# lfovca-rev2.net
KiCad netlist of a schematic drawn in EAGLE
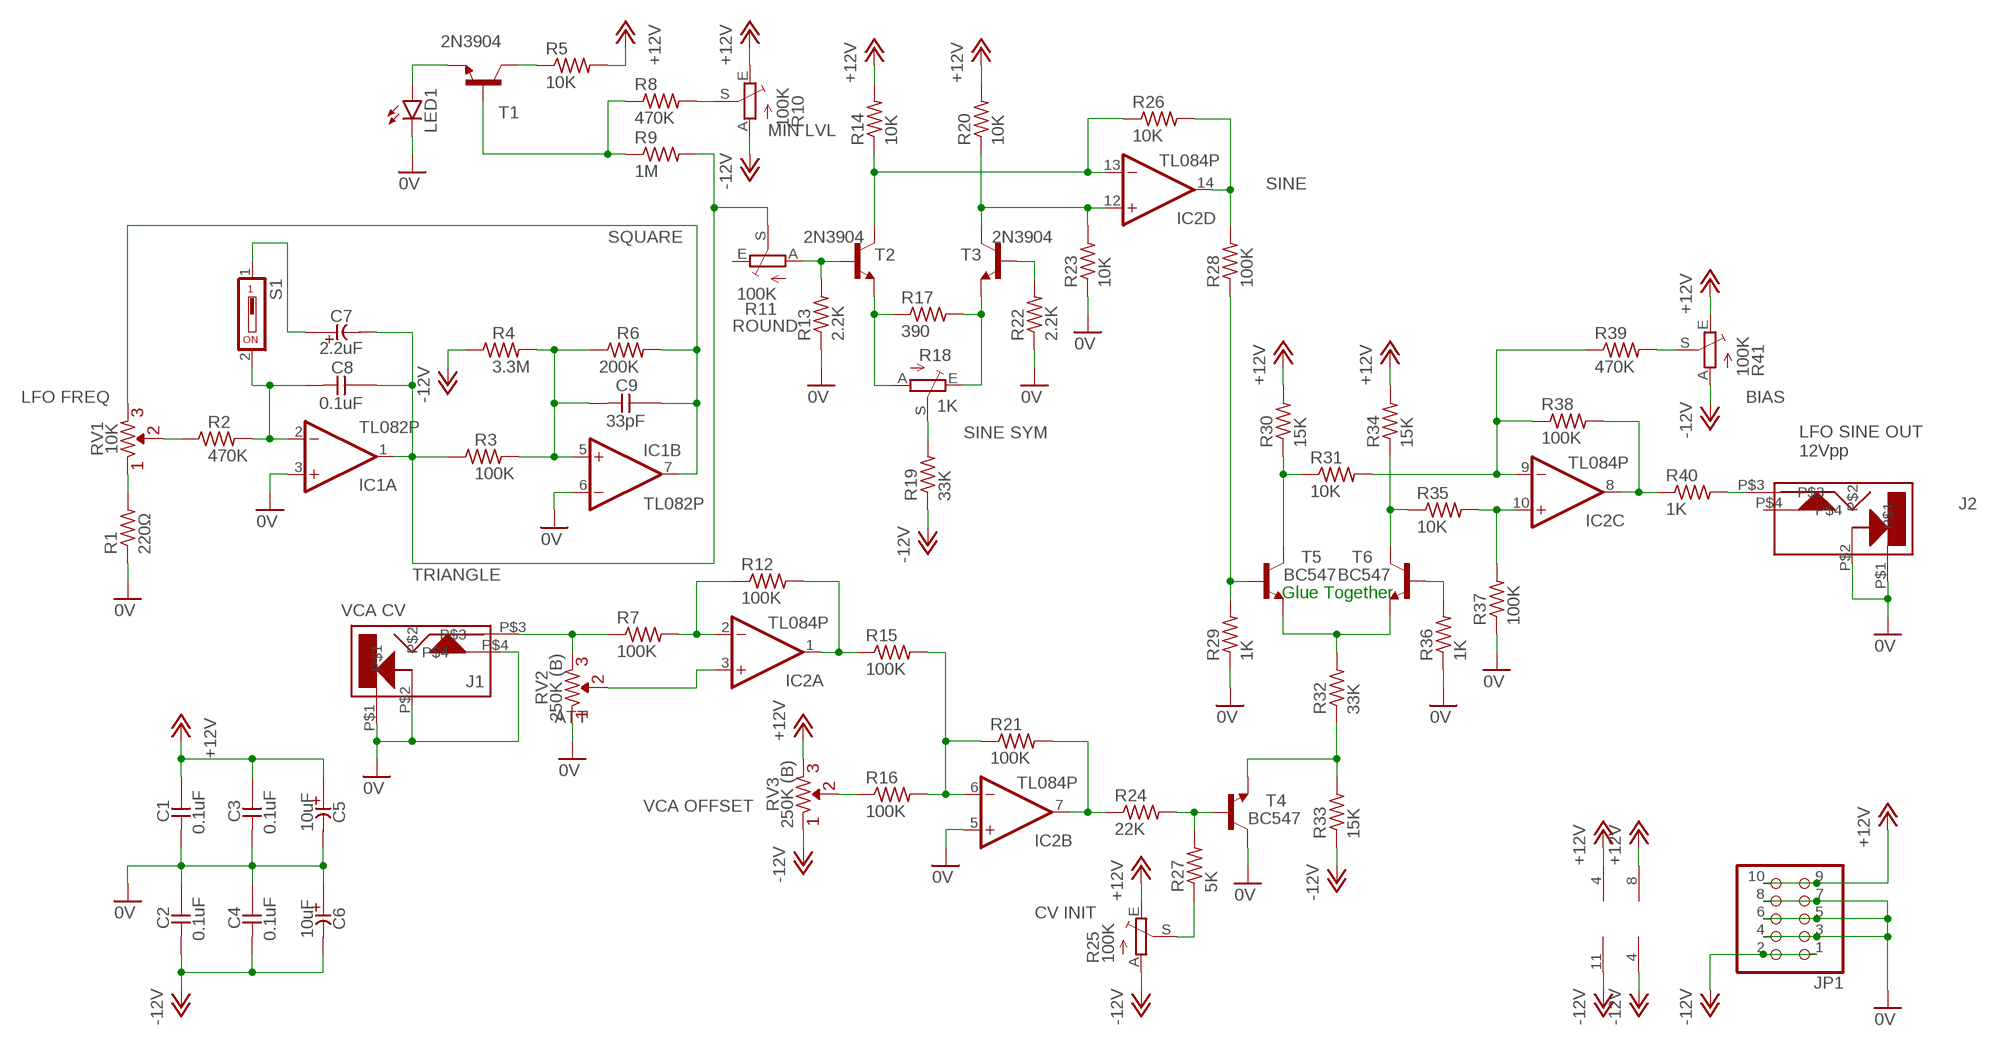
[diagram p0: schematic, sheet 1]

(export (version "E")
  (design (tool "Eeschema 10.0.6"))
  (components
    (comp (ref "C1")
      (value "0.1uF")
      (footprint "eagle-import:C025-024X044")
      (libsource (lib "eagle-import") (part "CC-US025-024X044"))
    )
    (comp (ref "C2")
      (value "0.1uF")
      (footprint "eagle-import:C025-024X044")
      (libsource (lib "eagle-import") (part "CC-US025-024X044"))
    )
    (comp (ref "C3")
      (value "0.1uF")
      (footprint "eagle-import:C025-024X044")
      (libsource (lib "eagle-import") (part "CC-US025-024X044"))
    )
    (comp (ref "C4")
      (value "0.1uF")
      (footprint "eagle-import:C025-024X044")
      (libsource (lib "eagle-import") (part "CC-US025-024X044"))
    )
    (comp (ref "C5")
      (value "10uF")
      (footprint "eagle-import:E2-5")
      (libsource (lib "eagle-import") (part "CE-USE2-5"))
    )
    (comp (ref "C6")
      (value "10uF")
      (footprint "eagle-import:E2-5")
      (libsource (lib "eagle-import") (part "CE-USE2-5"))
    )
    (comp (ref "C7")
      (value "2.2uF")
      (footprint "eagle-import:E2-5")
      (libsource (lib "eagle-import") (part "CE-USE2-5"))
    )
    (comp (ref "C8")
      (value "0.1uF")
      (footprint "eagle-import:C025-024X044")
      (libsource (lib "eagle-import") (part "CC-US025-024X044"))
    )
    (comp (ref "C9")
      (value "33pF")
      (footprint "eagle-import:C025-024X044")
      (libsource (lib "eagle-import") (part "CC-US025-024X044"))
    )
    (comp (ref "IC1")
      (value "TL082P")
      (footprint "eagle-import:DIL08")
      (libsource (lib "eagle-import") (part "TL082P"))
    )
    (comp (ref "IC2")
      (value "TL084P")
      (footprint "eagle-import:DIL14")
      (libsource (lib "eagle-import") (part "TL084P"))
    )
    (comp (ref "J1")
      (value "CL1384")
      (footprint "eagle-import:CL1384")
      (libsource (lib "eagle-import") (part "CL1384"))
    )
    (comp (ref "J2")
      (value "CL1384")
      (footprint "eagle-import:CL1384")
      (libsource (lib "eagle-import") (part "CL1384"))
    )
    (comp (ref "JP1")
      (value "PINHD-2X5")
      (footprint "eagle-import:2X05")
      (libsource (lib "eagle-import") (part "PINHD-2X5"))
    )
    (comp (ref "LED1")
      (value "LED3MM")
      (footprint "eagle-import:LED3MM")
      (libsource (lib "eagle-import") (part "LED3MM"))
    )
    (comp (ref "R1")
      (value "220Ω")
      (footprint "eagle-import:0207_7")
      (libsource (lib "eagle-import") (part "R-US_0207/7"))
    )
    (comp (ref "R2")
      (value "470K")
      (footprint "eagle-import:0207_7")
      (libsource (lib "eagle-import") (part "R-US_0207/7"))
    )
    (comp (ref "R3")
      (value "100K")
      (footprint "eagle-import:0207_7")
      (libsource (lib "eagle-import") (part "R-US_0207/7"))
    )
    (comp (ref "R4")
      (value "3.3M")
      (footprint "eagle-import:0207_7")
      (libsource (lib "eagle-import") (part "R-US_0207/7"))
    )
    (comp (ref "R5")
      (value "10K")
      (footprint "eagle-import:0207_7")
      (libsource (lib "eagle-import") (part "R-US_0207/7"))
    )
    (comp (ref "R6")
      (value "200K")
      (footprint "eagle-import:0207_7")
      (libsource (lib "eagle-import") (part "R-US_0207/7"))
    )
    (comp (ref "R7")
      (value "100K")
      (footprint "eagle-import:0207_7")
      (libsource (lib "eagle-import") (part "R-US_0207/7"))
    )
    (comp (ref "R8")
      (value "470K")
      (footprint "eagle-import:0207_7")
      (libsource (lib "eagle-import") (part "R-US_0207/7"))
    )
    (comp (ref "R9")
      (value "1M")
      (footprint "eagle-import:0207_7")
      (libsource (lib "eagle-import") (part "R-US_0207/7"))
    )
    (comp (ref "R10")
      (value "100K")
      (footprint "eagle-import:CA6V")
      (libsource (lib "eagle-import") (part "TRIM_EU-CA6V"))
    )
    (comp (ref "R11")
      (value "100K")
      (footprint "eagle-import:CA6V")
      (libsource (lib "eagle-import") (part "TRIM_EU-CA6V"))
    )
    (comp (ref "R12")
      (value "100K")
      (footprint "eagle-import:0207_7")
      (libsource (lib "eagle-import") (part "R-US_0207/7"))
    )
    (comp (ref "R13")
      (value "2.2K")
      (footprint "eagle-import:0207_7")
      (libsource (lib "eagle-import") (part "R-US_0207/7"))
    )
    (comp (ref "R14")
      (value "10K")
      (footprint "eagle-import:0207_7")
      (libsource (lib "eagle-import") (part "R-US_0207/7"))
    )
    (comp (ref "R15")
      (value "100K")
      (footprint "eagle-import:0207_7")
      (libsource (lib "eagle-import") (part "R-US_0207/7"))
    )
    (comp (ref "R16")
      (value "100K")
      (footprint "eagle-import:0207_7")
      (libsource (lib "eagle-import") (part "R-US_0207/7"))
    )
    (comp (ref "R17")
      (value "390")
      (footprint "eagle-import:0207_7")
      (libsource (lib "eagle-import") (part "R-US_0207/7"))
    )
    (comp (ref "R18")
      (value "1K")
      (footprint "eagle-import:CA6V")
      (libsource (lib "eagle-import") (part "TRIM_EU-CA6V"))
    )
    (comp (ref "R19")
      (value "33K")
      (footprint "eagle-import:0207_7")
      (libsource (lib "eagle-import") (part "R-US_0207/7"))
    )
    (comp (ref "R20")
      (value "10K")
      (footprint "eagle-import:0207_7")
      (libsource (lib "eagle-import") (part "R-US_0207/7"))
    )
    (comp (ref "R21")
      (value "100K")
      (footprint "eagle-import:0207_7")
      (libsource (lib "eagle-import") (part "R-US_0207/7"))
    )
    (comp (ref "R22")
      (value "2.2K")
      (footprint "eagle-import:0207_7")
      (libsource (lib "eagle-import") (part "R-US_0207/7"))
    )
    (comp (ref "R23")
      (value "10K")
      (footprint "eagle-import:0207_7")
      (libsource (lib "eagle-import") (part "R-US_0207/7"))
    )
    (comp (ref "R24")
      (value "22K")
      (footprint "eagle-import:0207_7")
      (libsource (lib "eagle-import") (part "R-US_0207/7"))
    )
    (comp (ref "R25")
      (value "100K")
      (footprint "eagle-import:CA6V")
      (libsource (lib "eagle-import") (part "TRIM_EU-CA6V"))
    )
    (comp (ref "R26")
      (value "10K")
      (footprint "eagle-import:0207_7")
      (libsource (lib "eagle-import") (part "R-US_0207/7"))
    )
    (comp (ref "R27")
      (value "5K")
      (footprint "eagle-import:0207_7")
      (libsource (lib "eagle-import") (part "R-US_0207/7"))
    )
    (comp (ref "R28")
      (value "100K")
      (footprint "eagle-import:0207_7")
      (libsource (lib "eagle-import") (part "R-US_0207/7"))
    )
    (comp (ref "R29")
      (value "1K")
      (footprint "eagle-import:0207_7")
      (libsource (lib "eagle-import") (part "R-US_0207/7"))
    )
    (comp (ref "R30")
      (value "15K")
      (footprint "eagle-import:0207_7")
      (libsource (lib "eagle-import") (part "R-US_0207/7"))
    )
    (comp (ref "R31")
      (value "10K")
      (footprint "eagle-import:0207_7")
      (libsource (lib "eagle-import") (part "R-US_0207/7"))
    )
    (comp (ref "R32")
      (value "33K")
      (footprint "eagle-import:0207_7")
      (libsource (lib "eagle-import") (part "R-US_0207/7"))
    )
    (comp (ref "R33")
      (value "15K")
      (footprint "eagle-import:0207_7")
      (libsource (lib "eagle-import") (part "R-US_0207/7"))
    )
    (comp (ref "R34")
      (value "15K")
      (footprint "eagle-import:0207_7")
      (libsource (lib "eagle-import") (part "R-US_0207/7"))
    )
    (comp (ref "R35")
      (value "10K")
      (footprint "eagle-import:0207_7")
      (libsource (lib "eagle-import") (part "R-US_0207/7"))
    )
    (comp (ref "R36")
      (value "1K")
      (footprint "eagle-import:0207_7")
      (libsource (lib "eagle-import") (part "R-US_0207/7"))
    )
    (comp (ref "R37")
      (value "100K")
      (footprint "eagle-import:0207_7")
      (libsource (lib "eagle-import") (part "R-US_0207/7"))
    )
    (comp (ref "R38")
      (value "100K")
      (footprint "eagle-import:0207_7")
      (libsource (lib "eagle-import") (part "R-US_0207/7"))
    )
    (comp (ref "R39")
      (value "470K")
      (footprint "eagle-import:0207_7")
      (libsource (lib "eagle-import") (part "R-US_0207/7"))
    )
    (comp (ref "R40")
      (value "1K")
      (footprint "eagle-import:0207_7")
      (libsource (lib "eagle-import") (part "R-US_0207/7"))
    )
    (comp (ref "R41")
      (value "100K")
      (footprint "eagle-import:CA6V")
      (libsource (lib "eagle-import") (part "TRIM_EU-CA6V"))
    )
    (comp (ref "RV1")
      (value "10K")
      (footprint "eagle-import:_COMMON_3RP_1610N")
      (libsource (lib "eagle-import") (part "R-VARR-VAR-10"))
    )
    (comp (ref "RV2")
      (value "250K (B)")
      (footprint "eagle-import:_COMMON_3RP_1610N")
      (libsource (lib "eagle-import") (part "R-VARR-VAR-10"))
    )
    (comp (ref "RV3")
      (value "250K (B)")
      (footprint "eagle-import:_COMMON_3RP_1610N")
      (libsource (lib "eagle-import") (part "R-VARR-VAR-10"))
    )
    (comp (ref "S1")
      (value "DS01")
      (footprint "eagle-import:DS-01")
      (libsource (lib "eagle-import") (part "DS01"))
    )
    (comp (ref "T1")
      (value "2N3904")
      (footprint "eagle-import:TO92-EBC")
      (libsource (lib "eagle-import") (part "-NPN-TO92-EBC2N3904"))
    )
    (comp (ref "T2")
      (value "2N3904")
      (footprint "eagle-import:TO92-EBC")
      (libsource (lib "eagle-import") (part "-NPN-TO92-EBC2N3904"))
    )
    (comp (ref "T3")
      (value "2N3904")
      (footprint "eagle-import:TO92-EBC")
      (libsource (lib "eagle-import") (part "-NPN-TO92-EBC2N3904"))
    )
    (comp (ref "T4")
      (value "BC547")
      (footprint "eagle-import:TO92-CBE")
      (libsource (lib "eagle-import") (part "-NPN-TO92-CBEBC547"))
    )
    (comp (ref "T5")
      (value "BC547")
      (footprint "eagle-import:TO92-CBE")
      (libsource (lib "eagle-import") (part "-NPN-TO92-CBEBC547"))
    )
    (comp (ref "T6")
      (value "BC547")
      (footprint "eagle-import:TO92-CBE")
      (libsource (lib "eagle-import") (part "-NPN-TO92-CBEBC547"))
    )
  )
  (nets
    (net (code "1") (name "+12V") (class "Default")
      (node (ref "C1") (pin "1") (pinfunction "1_1") (pintype "passive"))
      (node (ref "C3") (pin "1") (pinfunction "1_1") (pintype "passive"))
      (node (ref "C5") (pin "+") (pinfunction "+_+") (pintype "passive"))
      (node (ref "IC1") (pin "8") (pinfunction "V+_8") (pintype "power_in"))
      (node (ref "IC2") (pin "4") (pinfunction "V+_4") (pintype "power_in"))
      (node (ref "JP1") (pin "10") (pinfunction "10_10") (pintype "passive"))
      (node (ref "JP1") (pin "9") (pinfunction "9_9") (pintype "passive"))
      (node (ref "R10") (pin "E") (pinfunction "E_E") (pintype "passive"))
      (node (ref "R14") (pin "2") (pinfunction "2_2") (pintype "passive"))
      (node (ref "R20") (pin "2") (pinfunction "2_2") (pintype "passive"))
      (node (ref "R25") (pin "E") (pinfunction "E_E") (pintype "passive"))
      (node (ref "R30") (pin "2") (pinfunction "2_2") (pintype "passive"))
      (node (ref "R34") (pin "2") (pinfunction "2_2") (pintype "passive"))
      (node (ref "R41") (pin "E") (pinfunction "E_E") (pintype "passive"))
      (node (ref "R5") (pin "2") (pinfunction "2_2") (pintype "passive"))
      (node (ref "RV3") (pin "2") (pinfunction "2_2") (pintype "passive"))
    )
    (net (code "2") (name "-12V") (class "Default")
      (node (ref "C2") (pin "2") (pinfunction "2_2") (pintype "passive"))
      (node (ref "C4") (pin "2") (pinfunction "2_2") (pintype "passive"))
      (node (ref "C6") (pin "-") (pinfunction "-_-") (pintype "passive"))
      (node (ref "IC1") (pin "4") (pinfunction "V-_4") (pintype "power_in"))
      (node (ref "IC2") (pin "11") (pinfunction "V-_11") (pintype "power_in"))
      (node (ref "JP1") (pin "1") (pinfunction "1_1") (pintype "passive"))
      (node (ref "JP1") (pin "2") (pinfunction "2_2") (pintype "passive"))
      (node (ref "R10") (pin "A") (pinfunction "A_A") (pintype "passive"))
      (node (ref "R19") (pin "1") (pinfunction "1_1") (pintype "passive"))
      (node (ref "R25") (pin "A") (pinfunction "A_A") (pintype "passive"))
      (node (ref "R33") (pin "1") (pinfunction "1_1") (pintype "passive"))
      (node (ref "R4") (pin "1") (pinfunction "1_1") (pintype "passive"))
      (node (ref "R41") (pin "A") (pinfunction "A_A") (pintype "passive"))
      (node (ref "RV3") (pin "1") (pinfunction "1_1") (pintype "passive"))
    )
    (net (code "3") (name "0V") (class "Default")
      (node (ref "C1") (pin "2") (pinfunction "2_2") (pintype "passive"))
      (node (ref "C2") (pin "1") (pinfunction "1_1") (pintype "passive"))
      (node (ref "C3") (pin "2") (pinfunction "2_2") (pintype "passive"))
      (node (ref "C4") (pin "1") (pinfunction "1_1") (pintype "passive"))
      (node (ref "C5") (pin "-") (pinfunction "-_-") (pintype "passive"))
      (node (ref "C6") (pin "+") (pinfunction "+_+") (pintype "passive"))
      (node (ref "IC1") (pin "3") (pinfunction "+IN_3") (pintype "input"))
      (node (ref "IC1") (pin "6") (pinfunction "-IN_6") (pintype "input"))
      (node (ref "IC2") (pin "5") (pinfunction "+IN_5") (pintype "input"))
      (node (ref "J1") (pin "P$1") (pinfunction "P$1_P$1") (pintype "bidirectional"))
      (node (ref "J1") (pin "P$2") (pinfunction "P$2_P$2") (pintype "bidirectional"))
      (node (ref "J1") (pin "P$4") (pinfunction "P$4_P$4") (pintype "bidirectional"))
      (node (ref "J2") (pin "P$1") (pinfunction "P$1_P$1") (pintype "bidirectional"))
      (node (ref "J2") (pin "P$2") (pinfunction "P$2_P$2") (pintype "bidirectional"))
      (node (ref "JP1") (pin "3") (pinfunction "3_3") (pintype "passive"))
      (node (ref "JP1") (pin "4") (pinfunction "4_4") (pintype "passive"))
      (node (ref "JP1") (pin "5") (pinfunction "5_5") (pintype "passive"))
      (node (ref "JP1") (pin "6") (pinfunction "6_6") (pintype "passive"))
      (node (ref "JP1") (pin "7") (pinfunction "7_7") (pintype "passive"))
      (node (ref "JP1") (pin "8") (pinfunction "8_8") (pintype "passive"))
      (node (ref "LED1") (pin "K") (pinfunction "C_K") (pintype "passive"))
      (node (ref "R1") (pin "1") (pinfunction "1_1") (pintype "passive"))
      (node (ref "R13") (pin "1") (pinfunction "1_1") (pintype "passive"))
      (node (ref "R22") (pin "1") (pinfunction "1_1") (pintype "passive"))
      (node (ref "R23") (pin "1") (pinfunction "1_1") (pintype "passive"))
      (node (ref "R29") (pin "1") (pinfunction "1_1") (pintype "passive"))
      (node (ref "R36") (pin "1") (pinfunction "1_1") (pintype "passive"))
      (node (ref "R37") (pin "1") (pinfunction "1_1") (pintype "passive"))
      (node (ref "RV2") (pin "1") (pinfunction "1_1") (pintype "passive"))
      (node (ref "T4") (pin "C") (pinfunction "C_C") (pintype "passive"))
    )
    (net (code "4") (name "Net-(C7-Pad+)") (class "Default")
      (node (ref "C7") (pin "+") (pinfunction "+_+") (pintype "passive"))
      (node (ref "S1") (pin "1") (pinfunction "1_1") (pintype "passive"))
    )
    (net (code "5") (name "Net-(IC1A--IN)") (class "Default")
      (node (ref "C8") (pin "2") (pinfunction "2_2") (pintype "passive"))
      (node (ref "IC1") (pin "2") (pinfunction "-IN_2") (pintype "input"))
      (node (ref "R2") (pin "2") (pinfunction "2_2") (pintype "passive"))
      (node (ref "S1") (pin "2") (pinfunction "2_2") (pintype "passive"))
    )
    (net (code "6") (name "Net-(IC1A-OUT)") (class "Default")
      (node (ref "C7") (pin "-") (pinfunction "-_-") (pintype "passive"))
      (node (ref "C8") (pin "1") (pinfunction "1_1") (pintype "passive"))
      (node (ref "IC1") (pin "1") (pinfunction "OUT_1") (pintype "output"))
      (node (ref "R11") (pin "S") (pinfunction "S_S") (pintype "passive"))
      (node (ref "R3") (pin "1") (pinfunction "1_1") (pintype "passive"))
      (node (ref "R9") (pin "2") (pinfunction "2_2") (pintype "passive"))
    )
    (net (code "7") (name "Net-(IC1B-+IN)") (class "Default")
      (node (ref "C9") (pin "2") (pinfunction "2_2") (pintype "passive"))
      (node (ref "IC1") (pin "5") (pinfunction "+IN_5") (pintype "input"))
      (node (ref "R3") (pin "2") (pinfunction "2_2") (pintype "passive"))
      (node (ref "R4") (pin "2") (pinfunction "2_2") (pintype "passive"))
      (node (ref "R6") (pin "1") (pinfunction "1_1") (pintype "passive"))
    )
    (net (code "8") (name "Net-(IC1B-OUT)") (class "Default")
      (node (ref "C9") (pin "1") (pinfunction "1_1") (pintype "passive"))
      (node (ref "IC1") (pin "7") (pinfunction "OUT_7") (pintype "output"))
      (node (ref "R6") (pin "2") (pinfunction "2_2") (pintype "passive"))
      (node (ref "RV1") (pin "2") (pinfunction "2_2") (pintype "passive"))
    )
    (net (code "9") (name "Net-(IC2A-+IN)") (class "Default")
      (node (ref "IC2") (pin "3") (pinfunction "+IN_3") (pintype "input"))
      (node (ref "RV2") (pin "3") (pinfunction "P$1_3") (pintype "passive"))
    )
    (net (code "10") (name "Net-(IC2A--IN)") (class "Default")
      (node (ref "IC2") (pin "2") (pinfunction "-IN_2") (pintype "input"))
      (node (ref "R12") (pin "1") (pinfunction "1_1") (pintype "passive"))
      (node (ref "R7") (pin "2") (pinfunction "2_2") (pintype "passive"))
    )
    (net (code "11") (name "Net-(IC2A-OUT)") (class "Default")
      (node (ref "IC2") (pin "1") (pinfunction "OUT_1") (pintype "output"))
      (node (ref "R12") (pin "2") (pinfunction "2_2") (pintype "passive"))
      (node (ref "R15") (pin "1") (pinfunction "1_1") (pintype "passive"))
    )
    (net (code "12") (name "Net-(IC2B--IN)") (class "Default")
      (node (ref "IC2") (pin "6") (pinfunction "-IN_6") (pintype "input"))
      (node (ref "R15") (pin "2") (pinfunction "2_2") (pintype "passive"))
      (node (ref "R16") (pin "2") (pinfunction "2_2") (pintype "passive"))
      (node (ref "R21") (pin "1") (pinfunction "1_1") (pintype "passive"))
    )
    (net (code "13") (name "Net-(IC2B-OUT)") (class "Default")
      (node (ref "IC2") (pin "7") (pinfunction "OUT_7") (pintype "output"))
      (node (ref "R21") (pin "2") (pinfunction "2_2") (pintype "passive"))
      (node (ref "R24") (pin "1") (pinfunction "1_1") (pintype "passive"))
    )
    (net (code "14") (name "Net-(IC2C-+IN)") (class "Default")
      (node (ref "IC2") (pin "10") (pinfunction "+IN_10") (pintype "input"))
      (node (ref "R35") (pin "2") (pinfunction "2_2") (pintype "passive"))
      (node (ref "R37") (pin "2") (pinfunction "2_2") (pintype "passive"))
    )
    (net (code "15") (name "Net-(IC2C--IN)") (class "Default")
      (node (ref "IC2") (pin "9") (pinfunction "-IN_9") (pintype "input"))
      (node (ref "R31") (pin "2") (pinfunction "2_2") (pintype "passive"))
      (node (ref "R38") (pin "1") (pinfunction "1_1") (pintype "passive"))
      (node (ref "R39") (pin "1") (pinfunction "1_1") (pintype "passive"))
    )
    (net (code "16") (name "Net-(IC2C-OUT)") (class "Default")
      (node (ref "IC2") (pin "8") (pinfunction "OUT_8") (pintype "output"))
      (node (ref "R38") (pin "2") (pinfunction "2_2") (pintype "passive"))
      (node (ref "R40") (pin "1") (pinfunction "1_1") (pintype "passive"))
    )
    (net (code "17") (name "Net-(IC2D-+IN)") (class "Default")
      (node (ref "IC2") (pin "12") (pinfunction "+IN_12") (pintype "input"))
      (node (ref "R20") (pin "1") (pinfunction "1_1") (pintype "passive"))
      (node (ref "R23") (pin "2") (pinfunction "2_2") (pintype "passive"))
      (node (ref "T3") (pin "C") (pinfunction "C_C") (pintype "passive"))
    )
    (net (code "18") (name "Net-(IC2D--IN)") (class "Default")
      (node (ref "IC2") (pin "13") (pinfunction "-IN_13") (pintype "input"))
      (node (ref "R14") (pin "1") (pinfunction "1_1") (pintype "passive"))
      (node (ref "R26") (pin "1") (pinfunction "1_1") (pintype "passive"))
      (node (ref "T2") (pin "C") (pinfunction "C_C") (pintype "passive"))
    )
    (net (code "19") (name "Net-(IC2D-OUT)") (class "Default")
      (node (ref "IC2") (pin "14") (pinfunction "OUT_14") (pintype "output"))
      (node (ref "R26") (pin "2") (pinfunction "2_2") (pintype "passive"))
      (node (ref "R28") (pin "2") (pinfunction "2_2") (pintype "passive"))
    )
    (net (code "20") (name "Net-(J1-PadP$3)") (class "Default")
      (node (ref "J1") (pin "P$3") (pinfunction "P$3_P$3") (pintype "bidirectional"))
      (node (ref "R7") (pin "1") (pinfunction "1_1") (pintype "passive"))
      (node (ref "RV2") (pin "2") (pinfunction "2_2") (pintype "passive"))
    )
    (net (code "21") (name "Net-(J2-PadP$3)") (class "Default")
      (node (ref "J2") (pin "P$3") (pinfunction "P$3_P$3") (pintype "bidirectional"))
      (node (ref "R40") (pin "2") (pinfunction "2_2") (pintype "passive"))
    )
    (net (code "22") (name "Net-(LED1-PadA)") (class "Default")
      (node (ref "LED1") (pin "A") (pinfunction "A_A") (pintype "passive"))
      (node (ref "T1") (pin "E") (pinfunction "E_E") (pintype "passive"))
    )
    (net (code "23") (name "Net-(R1-Pad2)") (class "Default")
      (node (ref "R1") (pin "2") (pinfunction "2_2") (pintype "passive"))
      (node (ref "RV1") (pin "1") (pinfunction "1_1") (pintype "passive"))
    )
    (net (code "24") (name "Net-(R5-Pad1)") (class "Default")
      (node (ref "R5") (pin "1") (pinfunction "1_1") (pintype "passive"))
      (node (ref "T1") (pin "C") (pinfunction "C_C") (pintype "passive"))
    )
    (net (code "25") (name "Net-(R8-Pad1)") (class "Default")
      (node (ref "R8") (pin "1") (pinfunction "1_1") (pintype "passive"))
      (node (ref "R9") (pin "1") (pinfunction "1_1") (pintype "passive"))
      (node (ref "T1") (pin "B") (pinfunction "B_B") (pintype "passive"))
    )
    (net (code "26") (name "Net-(R10-PadS)") (class "Default")
      (node (ref "R10") (pin "S") (pinfunction "S_S") (pintype "passive"))
      (node (ref "R8") (pin "2") (pinfunction "2_2") (pintype "passive"))
    )
    (net (code "27") (name "Net-(R11-PadA)") (class "Default")
      (node (ref "R11") (pin "A") (pinfunction "A_A") (pintype "passive"))
      (node (ref "R13") (pin "2") (pinfunction "2_2") (pintype "passive"))
      (node (ref "T2") (pin "B") (pinfunction "B_B") (pintype "passive"))
    )
    (net (code "28") (name "Net-(R17-Pad1)") (class "Default")
      (node (ref "R17") (pin "1") (pinfunction "1_1") (pintype "passive"))
      (node (ref "R18") (pin "A") (pinfunction "A_A") (pintype "passive"))
      (node (ref "T2") (pin "E") (pinfunction "E_E") (pintype "passive"))
    )
    (net (code "29") (name "Net-(R17-Pad2)") (class "Default")
      (node (ref "R17") (pin "2") (pinfunction "2_2") (pintype "passive"))
      (node (ref "R18") (pin "E") (pinfunction "E_E") (pintype "passive"))
      (node (ref "T3") (pin "E") (pinfunction "E_E") (pintype "passive"))
    )
    (net (code "30") (name "Net-(R18-PadS)") (class "Default")
      (node (ref "R18") (pin "S") (pinfunction "S_S") (pintype "passive"))
      (node (ref "R19") (pin "2") (pinfunction "2_2") (pintype "passive"))
    )
    (net (code "31") (name "Net-(R22-Pad2)") (class "Default")
      (node (ref "R22") (pin "2") (pinfunction "2_2") (pintype "passive"))
      (node (ref "T3") (pin "B") (pinfunction "B_B") (pintype "passive"))
    )
    (net (code "32") (name "Net-(R24-Pad2)") (class "Default")
      (node (ref "R24") (pin "2") (pinfunction "2_2") (pintype "passive"))
      (node (ref "R27") (pin "2") (pinfunction "2_2") (pintype "passive"))
      (node (ref "T4") (pin "B") (pinfunction "B_B") (pintype "passive"))
    )
    (net (code "33") (name "Net-(R25-PadS)") (class "Default")
      (node (ref "R25") (pin "S") (pinfunction "S_S") (pintype "passive"))
      (node (ref "R27") (pin "1") (pinfunction "1_1") (pintype "passive"))
    )
    (net (code "34") (name "Net-(R28-Pad1)") (class "Default")
      (node (ref "R28") (pin "1") (pinfunction "1_1") (pintype "passive"))
      (node (ref "R29") (pin "2") (pinfunction "2_2") (pintype "passive"))
      (node (ref "T5") (pin "B") (pinfunction "B_B") (pintype "passive"))
    )
    (net (code "35") (name "Net-(R30-Pad1)") (class "Default")
      (node (ref "R30") (pin "1") (pinfunction "1_1") (pintype "passive"))
      (node (ref "R31") (pin "1") (pinfunction "1_1") (pintype "passive"))
      (node (ref "T5") (pin "C") (pinfunction "C_C") (pintype "passive"))
    )
    (net (code "36") (name "Net-(R32-Pad1)") (class "Default")
      (node (ref "R32") (pin "1") (pinfunction "1_1") (pintype "passive"))
      (node (ref "R33") (pin "2") (pinfunction "2_2") (pintype "passive"))
      (node (ref "T4") (pin "E") (pinfunction "E_E") (pintype "passive"))
    )
    (net (code "37") (name "Net-(R32-Pad2)") (class "Default")
      (node (ref "R32") (pin "2") (pinfunction "2_2") (pintype "passive"))
      (node (ref "T5") (pin "E") (pinfunction "E_E") (pintype "passive"))
      (node (ref "T6") (pin "E") (pinfunction "E_E") (pintype "passive"))
    )
    (net (code "38") (name "Net-(R34-Pad1)") (class "Default")
      (node (ref "R34") (pin "1") (pinfunction "1_1") (pintype "passive"))
      (node (ref "R35") (pin "1") (pinfunction "1_1") (pintype "passive"))
      (node (ref "T6") (pin "C") (pinfunction "C_C") (pintype "passive"))
    )
    (net (code "39") (name "Net-(R36-Pad2)") (class "Default")
      (node (ref "R36") (pin "2") (pinfunction "2_2") (pintype "passive"))
      (node (ref "T6") (pin "B") (pinfunction "B_B") (pintype "passive"))
    )
    (net (code "40") (name "Net-(R39-Pad2)") (class "Default")
      (node (ref "R39") (pin "2") (pinfunction "2_2") (pintype "passive"))
      (node (ref "R41") (pin "S") (pinfunction "S_S") (pintype "passive"))
    )
    (net (code "41") (name "Net-(RV1-P$1)") (class "Default")
      (node (ref "R2") (pin "1") (pinfunction "1_1") (pintype "passive"))
      (node (ref "RV1") (pin "3") (pinfunction "P$1_3") (pintype "passive"))
    )
    (net (code "42") (name "Net-(RV3-P$1)") (class "Default")
      (node (ref "R16") (pin "1") (pinfunction "1_1") (pintype "passive"))
      (node (ref "RV3") (pin "3") (pinfunction "P$1_3") (pintype "passive"))
    )
    (net (code "43") (name "unconnected-(J2-PadP$4)") (class "Default")
      (node (ref "J2") (pin "P$4") (pinfunction "P$4_P$4") (pintype "bidirectional"))
    )
    (net (code "44") (name "unconnected-(R11-PadE)") (class "Default")
      (node (ref "R11") (pin "E") (pinfunction "E_E") (pintype "passive"))
    )
  )
)
